# Filters.net
KiCad netlist of a schematic drawn in Altium Designer
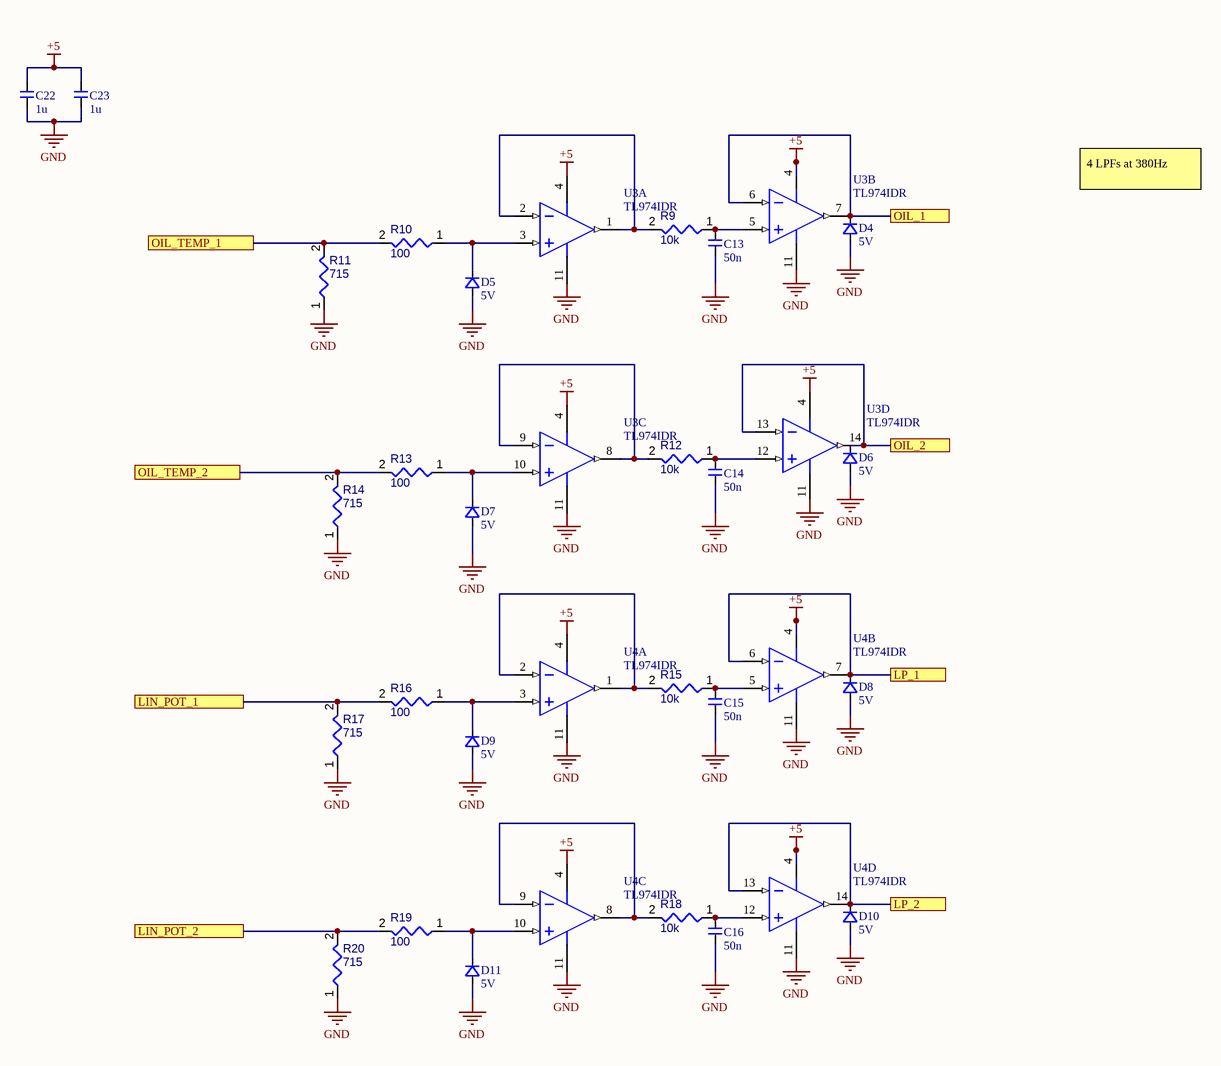
[diagram p0: Filters.SchDoc]

(export (version "E")
  (design (tool "Eeschema 10.0.6"))
  (components
    (comp (ref "C13")
      (value "50n")
      (footprint "CAP-0603")
      (fields (field (name "SOURCE") "ife19_Elec_Library.SchLib"))
      (libsource (lib "Illini Formula Electric") (part "CAP-0603"))
    )
    (comp (ref "C14")
      (value "50n")
      (footprint "CAP-0603")
      (fields (field (name "SOURCE") "ife19_Elec_Library.SchLib"))
      (libsource (lib "Illini Formula Electric") (part "CAP-0603"))
    )
    (comp (ref "C15")
      (value "50n")
      (footprint "CAP-0603")
      (fields (field (name "SOURCE") "ife19_Elec_Library.SchLib"))
      (libsource (lib "Illini Formula Electric") (part "CAP-0603"))
    )
    (comp (ref "C16")
      (value "50n")
      (footprint "CAP-0603")
      (fields (field (name "SOURCE") "ife19_Elec_Library.SchLib"))
      (libsource (lib "Illini Formula Electric") (part "CAP-0603"))
    )
    (comp (ref "C22")
      (value "1u")
      (footprint "CAP-0603")
      (fields (field (name "SOURCE") "ife19_Elec_Library.SchLib"))
      (libsource (lib "Illini Formula Electric") (part "CAP-0603"))
    )
    (comp (ref "C23")
      (value "1u")
      (footprint "CAP-0603")
      (fields (field (name "SOURCE") "ife19_Elec_Library.SchLib"))
      (libsource (lib "Illini Formula Electric") (part "CAP-0603"))
    )
    (comp (ref "D4")
      (value "5V")
      (footprint "SOD123")
      (fields (field (name "SOURCE") "ife19_Elec_Library.SchLib"))
      (libsource (lib "Illini Formula Electric") (part "DIODE-SOD323"))
    )
    (comp (ref "D5")
      (value "5V")
      (footprint "SOD123")
      (fields (field (name "SOURCE") "ife19_Elec_Library.SchLib"))
      (libsource (lib "Illini Formula Electric") (part "DIODE-SOD323"))
    )
    (comp (ref "D6")
      (value "5V")
      (footprint "SOD123")
      (fields (field (name "SOURCE") "ife19_Elec_Library.SchLib"))
      (libsource (lib "Illini Formula Electric") (part "DIODE-SOD323"))
    )
    (comp (ref "D7")
      (value "5V")
      (footprint "SOD123")
      (fields (field (name "SOURCE") "ife19_Elec_Library.SchLib"))
      (libsource (lib "Illini Formula Electric") (part "DIODE-SOD323"))
    )
    (comp (ref "D8")
      (value "5V")
      (footprint "SOD123")
      (fields (field (name "SOURCE") "ife19_Elec_Library.SchLib"))
      (libsource (lib "Illini Formula Electric") (part "DIODE-SOD323"))
    )
    (comp (ref "D9")
      (value "5V")
      (footprint "SOD123")
      (fields (field (name "SOURCE") "ife19_Elec_Library.SchLib"))
      (libsource (lib "Illini Formula Electric") (part "DIODE-SOD323"))
    )
    (comp (ref "D10")
      (value "5V")
      (footprint "SOD123")
      (fields (field (name "SOURCE") "ife19_Elec_Library.SchLib"))
      (libsource (lib "Illini Formula Electric") (part "DIODE-SOD323"))
    )
    (comp (ref "D11")
      (value "5V")
      (footprint "SOD123")
      (fields (field (name "SOURCE") "ife19_Elec_Library.SchLib"))
      (libsource (lib "Illini Formula Electric") (part "DIODE-SOD323"))
    )
    (comp (ref "R9")
      (value "10k")
      (footprint "RESC0805(2012)_L")
      (description "Chip Resistor, 120 Ohms, +/-5 %, 0.1 W, -55 to 155 degC, 0603")
      (fields
        (field (name "POWER") "100mW")
        (field (name "TOLERANCE") "5%")
        (field (name "AVAILABLE PREVIEW IMAGES") "2D")
      )
      (libsource (lib "Illini Formula Electric") (part "Symbol"))
    )
    (comp (ref "R10")
      (value "100")
      (footprint "RESC0805(2012)_L")
      (description "Chip Resistor, 120 Ohms, +/-5 %, 0.1 W, -55 to 155 degC, 0603")
      (fields
        (field (name "POWER") "100mW")
        (field (name "TOLERANCE") "5%")
        (field (name "AVAILABLE PREVIEW IMAGES") "2D")
      )
      (libsource (lib "Illini Formula Electric") (part "Symbol"))
    )
    (comp (ref "R11")
      (value "715")
      (footprint "RESC0805(2012)_L")
      (description "Chip Resistor, 120 Ohms, +/-5 %, 0.1 W, -55 to 155 degC, 0603")
      (fields
        (field (name "POWER") "100mW")
        (field (name "TOLERANCE") "5%")
        (field (name "AVAILABLE PREVIEW IMAGES") "2D")
      )
      (libsource (lib "Illini Formula Electric") (part "Symbol"))
    )
    (comp (ref "R12")
      (value "10k")
      (footprint "RESC0805(2012)_L")
      (description "Chip Resistor, 120 Ohms, +/-5 %, 0.1 W, -55 to 155 degC, 0603")
      (fields
        (field (name "POWER") "100mW")
        (field (name "TOLERANCE") "5%")
        (field (name "AVAILABLE PREVIEW IMAGES") "2D")
      )
      (libsource (lib "Illini Formula Electric") (part "Symbol"))
    )
    (comp (ref "R13")
      (value "100")
      (footprint "RESC0805(2012)_L")
      (description "Chip Resistor, 120 Ohms, +/-5 %, 0.1 W, -55 to 155 degC, 0603")
      (fields
        (field (name "POWER") "100mW")
        (field (name "TOLERANCE") "5%")
        (field (name "AVAILABLE PREVIEW IMAGES") "2D")
      )
      (libsource (lib "Illini Formula Electric") (part "Symbol"))
    )
    (comp (ref "R14")
      (value "715")
      (footprint "RESC0805(2012)_L")
      (description "Chip Resistor, 120 Ohms, +/-5 %, 0.1 W, -55 to 155 degC, 0603")
      (fields
        (field (name "POWER") "100mW")
        (field (name "TOLERANCE") "5%")
        (field (name "AVAILABLE PREVIEW IMAGES") "2D")
      )
      (libsource (lib "Illini Formula Electric") (part "Symbol"))
    )
    (comp (ref "R15")
      (value "10k")
      (footprint "RESC0805(2012)_L")
      (description "Chip Resistor, 120 Ohms, +/-5 %, 0.1 W, -55 to 155 degC, 0603")
      (fields
        (field (name "POWER") "100mW")
        (field (name "TOLERANCE") "5%")
        (field (name "AVAILABLE PREVIEW IMAGES") "2D")
      )
      (libsource (lib "Illini Formula Electric") (part "Symbol"))
    )
    (comp (ref "R16")
      (value "100")
      (footprint "RESC0805(2012)_L")
      (description "Chip Resistor, 120 Ohms, +/-5 %, 0.1 W, -55 to 155 degC, 0603")
      (fields
        (field (name "POWER") "100mW")
        (field (name "TOLERANCE") "5%")
        (field (name "AVAILABLE PREVIEW IMAGES") "2D")
      )
      (libsource (lib "Illini Formula Electric") (part "Symbol"))
    )
    (comp (ref "R17")
      (value "715")
      (footprint "RESC0805(2012)_L")
      (description "Chip Resistor, 120 Ohms, +/-5 %, 0.1 W, -55 to 155 degC, 0603")
      (fields
        (field (name "POWER") "100mW")
        (field (name "TOLERANCE") "5%")
        (field (name "AVAILABLE PREVIEW IMAGES") "2D")
      )
      (libsource (lib "Illini Formula Electric") (part "Symbol"))
    )
    (comp (ref "R18")
      (value "10k")
      (footprint "RESC0805(2012)_L")
      (description "Chip Resistor, 120 Ohms, +/-5 %, 0.1 W, -55 to 155 degC, 0603")
      (fields
        (field (name "POWER") "100mW")
        (field (name "TOLERANCE") "5%")
        (field (name "AVAILABLE PREVIEW IMAGES") "2D")
      )
      (libsource (lib "Illini Formula Electric") (part "Symbol"))
    )
    (comp (ref "R19")
      (value "100")
      (footprint "RESC0805(2012)_L")
      (description "Chip Resistor, 120 Ohms, +/-5 %, 0.1 W, -55 to 155 degC, 0603")
      (fields
        (field (name "POWER") "100mW")
        (field (name "TOLERANCE") "5%")
        (field (name "AVAILABLE PREVIEW IMAGES") "2D")
      )
      (libsource (lib "Illini Formula Electric") (part "Symbol"))
    )
    (comp (ref "R20")
      (value "715")
      (footprint "RESC0805(2012)_L")
      (description "Chip Resistor, 120 Ohms, +/-5 %, 0.1 W, -55 to 155 degC, 0603")
      (fields
        (field (name "POWER") "100mW")
        (field (name "TOLERANCE") "5%")
        (field (name "AVAILABLE PREVIEW IMAGES") "2D")
      )
      (libsource (lib "Illini Formula Electric") (part "Symbol"))
    )
    (comp (ref "U3")
      (value "TL974IDR")
      (footprint "D0014A_M")
      (fields (field (name "MANUFACTURER") "Texas Instruments"))
      (libsource (lib "Altium Content Vault") (part "TI-TLXX4X_MC3403-X14"))
    )
    (comp (ref "U4")
      (value "TL974IDR")
      (footprint "D0014A_M")
      (fields (field (name "MANUFACTURER") "Texas Instruments"))
      (libsource (lib "Altium Content Vault") (part "TI-TLXX4X_MC3403-X14"))
    )
  )
  (nets
    (net (code "1") (name "+5") (class "Default")
      (node (ref "C22") (pin "2") (pinfunction "2_2") (pintype "passive"))
      (node (ref "C23") (pin "2") (pinfunction "2_2") (pintype "passive"))
      (node (ref "U3") (pin "4") (pinfunction "VCC+_4") (pintype "power_in"))
      (node (ref "U4") (pin "4") (pinfunction "VCC+_4") (pintype "power_in"))
    )
    (net (code "2") (name "/LIN_POT_1") (class "Default")
      (node (ref "R16") (pin "2") (pinfunction "2_2") (pintype "passive"))
      (node (ref "R17") (pin "2") (pinfunction "2_2") (pintype "passive"))
    )
    (net (code "3") (name "/LIN_POT_2") (class "Default")
      (node (ref "R19") (pin "2") (pinfunction "2_2") (pintype "passive"))
      (node (ref "R20") (pin "2") (pinfunction "2_2") (pintype "passive"))
    )
    (net (code "4") (name "/LP_1") (class "Default")
      (node (ref "D8") (pin "K") (pinfunction "K_K") (pintype "passive"))
      (node (ref "U4") (pin "6") (pinfunction "IN2-_6") (pintype "input"))
      (node (ref "U4") (pin "7") (pinfunction "OUT2_7") (pintype "output"))
    )
    (net (code "5") (name "/LP_2") (class "Default")
      (node (ref "D10") (pin "K") (pinfunction "K_K") (pintype "passive"))
      (node (ref "U4") (pin "13") (pinfunction "IN4-_13") (pintype "input"))
      (node (ref "U4") (pin "14") (pinfunction "OUT4_14") (pintype "output"))
    )
    (net (code "6") (name "/OIL_1") (class "Default")
      (node (ref "D4") (pin "K") (pinfunction "K_K") (pintype "passive"))
      (node (ref "U3") (pin "6") (pinfunction "IN2-_6") (pintype "input"))
      (node (ref "U3") (pin "7") (pinfunction "OUT2_7") (pintype "output"))
    )
    (net (code "7") (name "/OIL_2") (class "Default")
      (node (ref "D6") (pin "K") (pinfunction "K_K") (pintype "passive"))
      (node (ref "U3") (pin "13") (pinfunction "IN4-_13") (pintype "input"))
      (node (ref "U3") (pin "14") (pinfunction "OUT4_14") (pintype "output"))
    )
    (net (code "8") (name "/OIL_TEMP_1") (class "Default")
      (node (ref "R10") (pin "2") (pinfunction "2_2") (pintype "passive"))
      (node (ref "R11") (pin "2") (pinfunction "2_2") (pintype "passive"))
    )
    (net (code "9") (name "/OIL_TEMP_2") (class "Default")
      (node (ref "R13") (pin "2") (pinfunction "2_2") (pintype "passive"))
      (node (ref "R14") (pin "2") (pinfunction "2_2") (pintype "passive"))
    )
    (net (code "10") (name "GND") (class "Default")
      (node (ref "C13") (pin "1") (pinfunction "1_1") (pintype "passive"))
      (node (ref "C14") (pin "1") (pinfunction "1_1") (pintype "passive"))
      (node (ref "C15") (pin "1") (pinfunction "1_1") (pintype "passive"))
      (node (ref "C16") (pin "1") (pinfunction "1_1") (pintype "passive"))
      (node (ref "C22") (pin "1") (pinfunction "1_1") (pintype "passive"))
      (node (ref "C23") (pin "1") (pinfunction "1_1") (pintype "passive"))
      (node (ref "D10") (pin "A") (pinfunction "A_A") (pintype "passive"))
      (node (ref "D11") (pin "A") (pinfunction "A_A") (pintype "passive"))
      (node (ref "D4") (pin "A") (pinfunction "A_A") (pintype "passive"))
      (node (ref "D5") (pin "A") (pinfunction "A_A") (pintype "passive"))
      (node (ref "D6") (pin "A") (pinfunction "A_A") (pintype "passive"))
      (node (ref "D7") (pin "A") (pinfunction "A_A") (pintype "passive"))
      (node (ref "D8") (pin "A") (pinfunction "A_A") (pintype "passive"))
      (node (ref "D9") (pin "A") (pinfunction "A_A") (pintype "passive"))
      (node (ref "R11") (pin "1") (pinfunction "1_1") (pintype "passive"))
      (node (ref "R14") (pin "1") (pinfunction "1_1") (pintype "passive"))
      (node (ref "R17") (pin "1") (pinfunction "1_1") (pintype "passive"))
      (node (ref "R20") (pin "1") (pinfunction "1_1") (pintype "passive"))
      (node (ref "U3") (pin "11") (pinfunction "VCC-_11") (pintype "power_in"))
      (node (ref "U4") (pin "11") (pinfunction "VCC-_11") (pintype "power_in"))
    )
    (net (code "11") (name "Net-(U3A-IN1+)") (class "Default")
      (node (ref "D5") (pin "K") (pinfunction "K_K") (pintype "passive"))
      (node (ref "R10") (pin "1") (pinfunction "1_1") (pintype "passive"))
      (node (ref "U3") (pin "3") (pinfunction "IN1+_3") (pintype "input"))
    )
    (net (code "12") (name "Net-(U3A-IN1-)") (class "Default")
      (node (ref "R9") (pin "2") (pinfunction "2_2") (pintype "passive"))
      (node (ref "U3") (pin "1") (pinfunction "OUT1_1") (pintype "output"))
      (node (ref "U3") (pin "2") (pinfunction "IN1-_2") (pintype "input"))
    )
    (net (code "13") (name "Net-(U3B-IN2+)") (class "Default")
      (node (ref "C13") (pin "2") (pinfunction "2_2") (pintype "passive"))
      (node (ref "R9") (pin "1") (pinfunction "1_1") (pintype "passive"))
      (node (ref "U3") (pin "5") (pinfunction "IN2+_5") (pintype "input"))
    )
    (net (code "14") (name "Net-(U3C-IN3+)") (class "Default")
      (node (ref "D7") (pin "K") (pinfunction "K_K") (pintype "passive"))
      (node (ref "R13") (pin "1") (pinfunction "1_1") (pintype "passive"))
      (node (ref "U3") (pin "10") (pinfunction "IN3+_10") (pintype "input"))
    )
    (net (code "15") (name "Net-(U3C-IN3-)") (class "Default")
      (node (ref "R12") (pin "2") (pinfunction "2_2") (pintype "passive"))
      (node (ref "U3") (pin "8") (pinfunction "OUT3_8") (pintype "output"))
      (node (ref "U3") (pin "9") (pinfunction "IN3-_9") (pintype "input"))
    )
    (net (code "16") (name "Net-(U3D-IN4+)") (class "Default")
      (node (ref "C14") (pin "2") (pinfunction "2_2") (pintype "passive"))
      (node (ref "R12") (pin "1") (pinfunction "1_1") (pintype "passive"))
      (node (ref "U3") (pin "12") (pinfunction "IN4+_12") (pintype "input"))
    )
    (net (code "17") (name "Net-(U4A-IN1+)") (class "Default")
      (node (ref "D9") (pin "K") (pinfunction "K_K") (pintype "passive"))
      (node (ref "R16") (pin "1") (pinfunction "1_1") (pintype "passive"))
      (node (ref "U4") (pin "3") (pinfunction "IN1+_3") (pintype "input"))
    )
    (net (code "18") (name "Net-(U4A-IN1-)") (class "Default")
      (node (ref "R15") (pin "2") (pinfunction "2_2") (pintype "passive"))
      (node (ref "U4") (pin "1") (pinfunction "OUT1_1") (pintype "output"))
      (node (ref "U4") (pin "2") (pinfunction "IN1-_2") (pintype "input"))
    )
    (net (code "19") (name "Net-(U4B-IN2+)") (class "Default")
      (node (ref "C15") (pin "2") (pinfunction "2_2") (pintype "passive"))
      (node (ref "R15") (pin "1") (pinfunction "1_1") (pintype "passive"))
      (node (ref "U4") (pin "5") (pinfunction "IN2+_5") (pintype "input"))
    )
    (net (code "20") (name "Net-(U4C-IN3+)") (class "Default")
      (node (ref "D11") (pin "K") (pinfunction "K_K") (pintype "passive"))
      (node (ref "R19") (pin "1") (pinfunction "1_1") (pintype "passive"))
      (node (ref "U4") (pin "10") (pinfunction "IN3+_10") (pintype "input"))
    )
    (net (code "21") (name "Net-(U4C-IN3-)") (class "Default")
      (node (ref "R18") (pin "2") (pinfunction "2_2") (pintype "passive"))
      (node (ref "U4") (pin "8") (pinfunction "OUT3_8") (pintype "output"))
      (node (ref "U4") (pin "9") (pinfunction "IN3-_9") (pintype "input"))
    )
    (net (code "22") (name "Net-(U4D-IN4+)") (class "Default")
      (node (ref "C16") (pin "2") (pinfunction "2_2") (pintype "passive"))
      (node (ref "R18") (pin "1") (pinfunction "1_1") (pintype "passive"))
      (node (ref "U4") (pin "12") (pinfunction "IN4+_12") (pintype "input"))
    )
  )
)
